# scs-check.net
KiCad netlist of a schematic drawn in Altium Designer
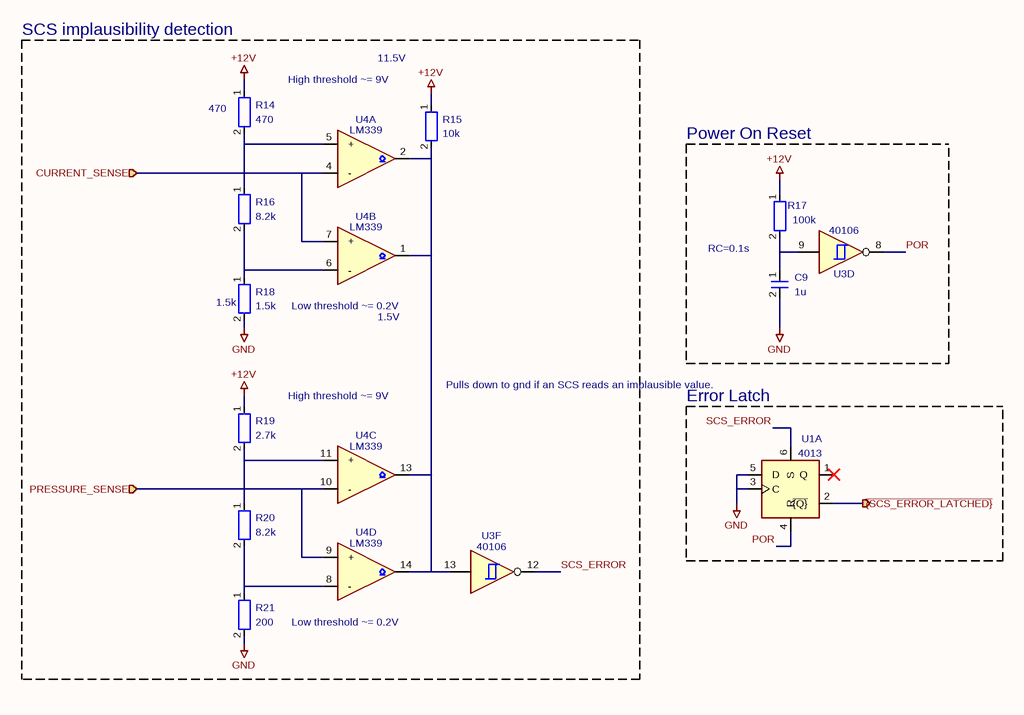
[diagram p0: scs-check.SchDoc]

(export (version "E")
  (design (tool "Eeschema 10.0.6"))
  (components
    (comp (ref "C9") (value "1u") (footprint "C_0603_1608Metric") (libsource (lib "Device") (part "C_Small")))
    (comp (ref "R14")
      (value "470")
      (footprint "R_0603_1608Metric")
      (fields (field (name "MOUSER PART NUMBER") "603-RT0603FRD07470RL"))
      (libsource (lib "Device") (part "R"))
    )
    (comp (ref "R15") (value "10k") (footprint "R_0603_1608Metric") (libsource (lib "Device") (part "R")))
    (comp (ref "R16")
      (value "8.2k")
      (footprint "R_0603_1608Metric")
      (fields (field (name "MOUSER PART NUMBER") "603-RT0603FRD078K2L"))
      (libsource (lib "Device") (part "R"))
    )
    (comp (ref "R17") (value "100k") (footprint "R_0603_1608Metric") (libsource (lib "Device") (part "R")))
    (comp (ref "R18")
      (value "1.5k")
      (footprint "R_0603_1608Metric")
      (fields (field (name "MOUSER PART NUMBER") "603-RT0603FRE071K5L"))
      (libsource (lib "Device") (part "R"))
    )
    (comp (ref "R19")
      (value "2.7k")
      (footprint "R_0603_1608Metric")
      (fields (field (name "MOUSER PART NUMBER") "603-RT0603FRE072K7L"))
      (libsource (lib "Device") (part "R"))
    )
    (comp (ref "R20")
      (value "8.2k")
      (footprint "R_0603_1608Metric")
      (fields (field (name "MOUSER PART NUMBER") "603-RT0603FRD078K2L"))
      (libsource (lib "Device") (part "R"))
    )
    (comp (ref "R21") (value "200") (footprint "R_0603_1608Metric") (libsource (lib "Device") (part "R")))
    (comp (ref "U1")
      (value "4013")
      (footprint "SOIC-14_3.9x8.7mm_P1.27mm")
      (libsource (lib "4xxx") (part "4013"))
    )
    (comp (ref "U3")
      (value "40106")
      (footprint "SOIC-14_3.9x8.7mm_P1.27mm")
      (libsource (lib "4xxx") (part "40106"))
    )
    (comp (ref "U4")
      (value "LM339")
      (footprint "SOIC-14_3.9x8.7mm_P1.27mm")
      (libsource (lib "Comparator") (part "LM339"))
    )
  )
  (nets
    (net (code "1") (name "+12V") (class "Default")
      (node (ref "R14") (pin "1") (pinfunction "1_1") (pintype "passive"))
      (node (ref "R15") (pin "1") (pinfunction "1_1") (pintype "passive"))
      (node (ref "R17") (pin "1") (pinfunction "1_1") (pintype "passive"))
      (node (ref "R19") (pin "1") (pinfunction "1_1") (pintype "passive"))
    )
    (net (code "2") (name "/CURRENT_SENSE") (class "Default")
      (node (ref "U4") (pin "4") (pinfunction "-_4") (pintype "passive"))
      (node (ref "U4") (pin "7") (pinfunction "+_7") (pintype "passive"))
    )
    (net (code "3") (name "/POR") (class "Default")
      (node (ref "U1") (pin "4") (pinfunction "R_4") (pintype "passive"))
      (node (ref "U3") (pin "8") (pinfunction "8_8") (pintype "passive"))
    )
    (net (code "4") (name "/PRESSURE_SENSE") (class "Default")
      (node (ref "U4") (pin "10") (pinfunction "-_10") (pintype "passive"))
      (node (ref "U4") (pin "9") (pinfunction "+_9") (pintype "passive"))
    )
    (net (code "5") (name "/SCS_ERROR") (class "Default")
      (node (ref "U1") (pin "6") (pinfunction "S_6") (pintype "passive"))
      (node (ref "U3") (pin "12") (pinfunction "12_12") (pintype "passive"))
    )
    (net (code "6") (name "/~{{SCS_ERROR_LATCHED}}") (class "Default")
      (node (ref "U1") (pin "2") (pinfunction "~{{Q}}_2") (pintype "passive"))
    )
    (net (code "7") (name "GND") (class "Default")
      (node (ref "C9") (pin "2") (pinfunction "2_2") (pintype "passive"))
      (node (ref "R18") (pin "2") (pinfunction "2_2") (pintype "passive"))
      (node (ref "R21") (pin "2") (pinfunction "2_2") (pintype "passive"))
      (node (ref "U1") (pin "3") (pinfunction "C_3") (pintype "passive"))
      (node (ref "U1") (pin "5") (pinfunction "D_5") (pintype "passive"))
    )
    (net (code "8") (name "Net-(C9-Pad1)") (class "Default")
      (node (ref "C9") (pin "1") (pinfunction "1_1") (pintype "passive"))
      (node (ref "R17") (pin "2") (pinfunction "2_2") (pintype "passive"))
      (node (ref "U3") (pin "9") (pinfunction "9_9") (pintype "passive"))
    )
    (net (code "9") (name "Net-(R15-Pad2)") (class "Default")
      (node (ref "R15") (pin "2") (pinfunction "2_2") (pintype "passive"))
      (node (ref "U3") (pin "13") (pinfunction "13_13") (pintype "passive"))
      (node (ref "U4") (pin "1") (pinfunction "1_1") (pintype "passive"))
      (node (ref "U4") (pin "13") (pinfunction "13_13") (pintype "passive"))
      (node (ref "U4") (pin "14") (pinfunction "14_14") (pintype "passive"))
      (node (ref "U4") (pin "2") (pinfunction "2_2") (pintype "passive"))
    )
    (net (code "10") (name "Net-(U4A-+)") (class "Default")
      (node (ref "R14") (pin "2") (pinfunction "2_2") (pintype "passive"))
      (node (ref "R16") (pin "1") (pinfunction "1_1") (pintype "passive"))
      (node (ref "U4") (pin "5") (pinfunction "+_5") (pintype "passive"))
    )
    (net (code "11") (name "Net-(U4B--)") (class "Default")
      (node (ref "R16") (pin "2") (pinfunction "2_2") (pintype "passive"))
      (node (ref "R18") (pin "1") (pinfunction "1_1") (pintype "passive"))
      (node (ref "U4") (pin "6") (pinfunction "-_6") (pintype "passive"))
    )
    (net (code "12") (name "Net-(U4C-+)") (class "Default")
      (node (ref "R19") (pin "2") (pinfunction "2_2") (pintype "passive"))
      (node (ref "R20") (pin "1") (pinfunction "1_1") (pintype "passive"))
      (node (ref "U4") (pin "11") (pinfunction "+_11") (pintype "passive"))
    )
    (net (code "13") (name "Net-(U4D--)") (class "Default")
      (node (ref "R20") (pin "2") (pinfunction "2_2") (pintype "passive"))
      (node (ref "R21") (pin "1") (pinfunction "1_1") (pintype "passive"))
      (node (ref "U4") (pin "8") (pinfunction "-_8") (pintype "passive"))
    )
    (net (code "14") (name "unconnected-(U1A-Q-Pad1)") (class "Default")
      (node (ref "U1") (pin "1") (pinfunction "Q_1") (pintype "passive+no_connect"))
    )
  )
)
